# USB_UART.net
KiCad netlist of a schematic drawn in Altium Designer
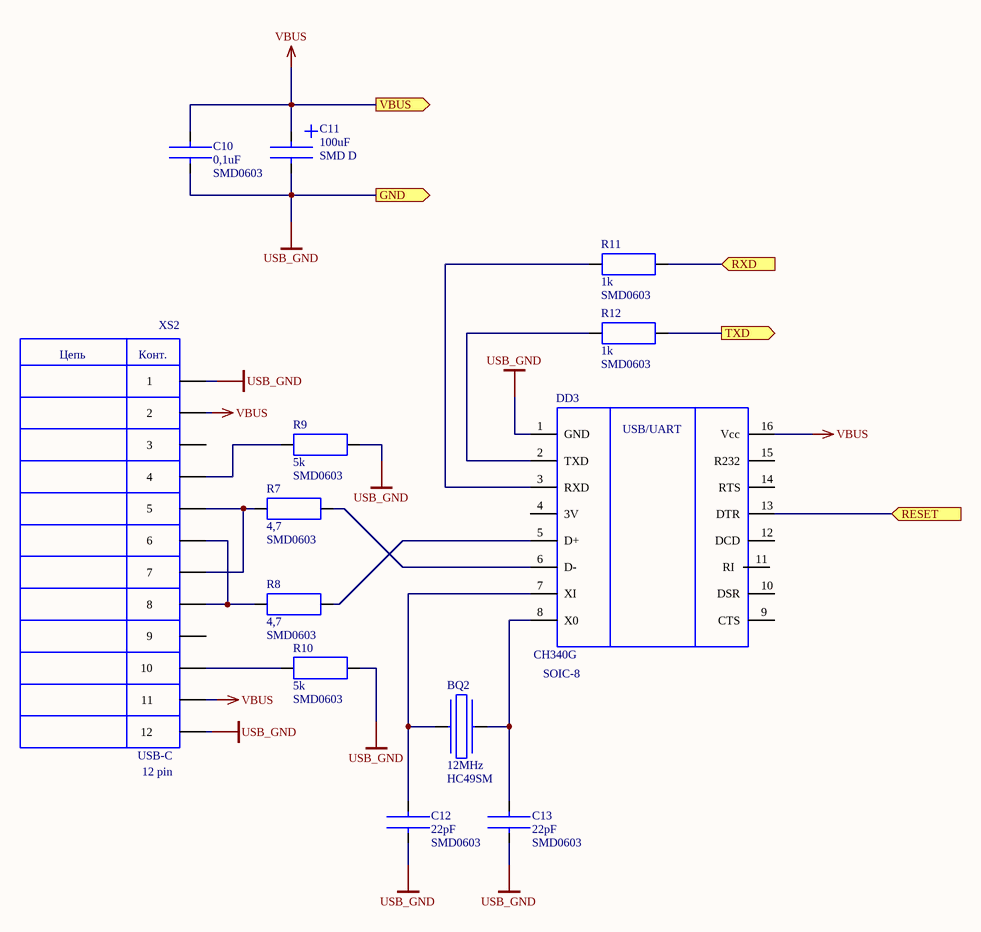
[diagram p0: USB_UART.SchDoc]

(export (version "E")
  (design (tool "Eeschema 10.0.6"))
  (components
    (comp (ref "BQ2")
      (value "12МHz")
      (footprint "BQ_HC49SM")
      (fields (field (name "PACKAGE") "HC49SM"))
      (libsource (lib "MechanikLibrary") (part "BQ_HC49SM"))
    )
    (comp (ref "C10")
      (value "0,1uF")
      (footprint "SMD0603(1005)")
      (fields (field (name "PACKAGE") "SMD0603"))
      (libsource (lib "MechanikLibrary") (part "CER_CUP_0603"))
    )
    (comp (ref "C11")
      (value "100uF")
      (footprint "TANT_CAP_D(7343)")
      (fields (field (name "PACKAGE") "SMD D"))
      (libsource (lib "MechanikLibrary") (part "C_TANT_D"))
    )
    (comp (ref "C12")
      (value "22pF")
      (footprint "SMD0603(1005)")
      (fields (field (name "PACKAGE") "SMD0603"))
      (libsource (lib "MechanikLibrary") (part "CER_CUP_0603"))
    )
    (comp (ref "C13")
      (value "22pF")
      (footprint "SMD0603(1005)")
      (fields (field (name "PACKAGE") "SMD0603"))
      (libsource (lib "MechanikLibrary") (part "CER_CUP_0603"))
    )
    (comp (ref "DD3")
      (value "CH340G")
      (footprint "SOIC16")
      (fields (field (name "PACKAGE") "SOIC-8"))
      (libsource (lib "MechanikLibrary") (part "Микросхема CH340G"))
    )
    (comp (ref "R7")
      (value "4,7")
      (footprint "SMD0603(1005)")
      (fields (field (name "PACKAGE") "SMD0603"))
      (libsource (lib "MechanikLibrary") (part "R_0603"))
    )
    (comp (ref "R8")
      (value "4,7")
      (footprint "SMD0603(1005)")
      (fields (field (name "PACKAGE") "SMD0603"))
      (libsource (lib "MechanikLibrary") (part "R_0603"))
    )
    (comp (ref "R9")
      (value "5k")
      (footprint "SMD0603(1005)")
      (fields (field (name "PACKAGE") "SMD0603"))
      (libsource (lib "MechanikLibrary") (part "R_0603"))
    )
    (comp (ref "R10")
      (value "5k")
      (footprint "SMD0603(1005)")
      (fields (field (name "PACKAGE") "SMD0603"))
      (libsource (lib "MechanikLibrary") (part "R_0603"))
    )
    (comp (ref "R11")
      (value "1k")
      (footprint "SMD0603(1005)")
      (fields (field (name "PACKAGE") "SMD0603"))
      (libsource (lib "MechanikLibrary") (part "R_0603"))
    )
    (comp (ref "R12")
      (value "1k")
      (footprint "SMD0603(1005)")
      (fields (field (name "PACKAGE") "SMD0603"))
      (libsource (lib "MechanikLibrary") (part "R_0603"))
    )
    (comp (ref "XS2")
      (value "USB-C")
      (footprint "USB_C")
      (fields (field (name "PACKAGE") "12 pin"))
      (libsource (lib "MechanikLibrary") (part "USB_C"))
    )
  )
  (nets
    (net (code "1") (name "/RESET") (class "Default")
      (node (ref "DD3") (pin "13") (pinfunction "DTR_13") (pintype "passive"))
    )
    (net (code "2") (name "/RXD") (class "Default") (node (ref "R11") (pin "1") (pintype "passive")))
    (net (code "3") (name "/TXD") (class "Default") (node (ref "R12") (pin "1") (pintype "passive")))
    (net (code "4") (name "Net-(DD3-D+)") (class "Default")
      (node (ref "DD3") (pin "5") (pinfunction "D+_5") (pintype "passive"))
      (node (ref "R8") (pin "2") (pintype "passive"))
    )
    (net (code "5") (name "Net-(DD3-D-)") (class "Default")
      (node (ref "DD3") (pin "6") (pinfunction "D-_6") (pintype "passive"))
      (node (ref "R7") (pin "2") (pintype "passive"))
    )
    (net (code "6") (name "Net-(DD3-RXD)") (class "Default")
      (node (ref "DD3") (pin "3") (pinfunction "RXD_3") (pintype "passive"))
      (node (ref "R11") (pin "2") (pintype "passive"))
    )
    (net (code "7") (name "Net-(DD3-TXD)") (class "Default")
      (node (ref "DD3") (pin "2") (pinfunction "TXD_2") (pintype "passive"))
      (node (ref "R12") (pin "2") (pintype "passive"))
    )
    (net (code "8") (name "Net-(DD3-X0)") (class "Default")
      (node (ref "BQ2") (pin "2") (pintype "passive"))
      (node (ref "C13") (pin "2") (pintype "passive"))
      (node (ref "DD3") (pin "8") (pinfunction "X0_8") (pintype "passive"))
    )
    (net (code "9") (name "Net-(DD3-XI)") (class "Default")
      (node (ref "BQ2") (pin "1") (pintype "passive"))
      (node (ref "C12") (pin "2") (pintype "passive"))
      (node (ref "DD3") (pin "7") (pinfunction "XI_7") (pintype "passive"))
    )
    (net (code "10") (name "Net-(R7-Pad1)") (class "Default")
      (node (ref "R7") (pin "1") (pintype "passive"))
      (node (ref "XS2") (pin "5") (pinfunction "5_5") (pintype "passive"))
      (node (ref "XS2") (pin "7") (pinfunction "7_7") (pintype "passive"))
    )
    (net (code "11") (name "Net-(R8-Pad1)") (class "Default")
      (node (ref "R8") (pin "1") (pintype "passive"))
      (node (ref "XS2") (pin "6") (pinfunction "6_6") (pintype "passive"))
      (node (ref "XS2") (pin "8") (pinfunction "8_8") (pintype "passive"))
    )
    (net (code "12") (name "Net-(R9-Pad2)") (class "Default")
      (node (ref "R9") (pin "2") (pintype "passive"))
      (node (ref "XS2") (pin "4") (pinfunction "4_4") (pintype "passive"))
    )
    (net (code "13") (name "Net-(R10-Pad2)") (class "Default")
      (node (ref "R10") (pin "2") (pintype "passive"))
      (node (ref "XS2") (pin "10") (pinfunction "10_10") (pintype "passive"))
    )
    (net (code "14") (name "USB_GND") (class "Default")
      (node (ref "C10") (pin "1") (pintype "passive"))
      (node (ref "C11") (pin "2") (pintype "passive"))
      (node (ref "C12") (pin "1") (pintype "passive"))
      (node (ref "C13") (pin "1") (pintype "passive"))
      (node (ref "DD3") (pin "1") (pinfunction "GND_1") (pintype "passive"))
      (node (ref "R10") (pin "1") (pintype "passive"))
      (node (ref "R9") (pin "1") (pintype "passive"))
      (node (ref "XS2") (pin "1") (pinfunction "1_1") (pintype "passive"))
      (node (ref "XS2") (pin "12") (pinfunction "12_12") (pintype "passive"))
    )
    (net (code "15") (name "VBUS") (class "Default")
      (node (ref "C10") (pin "2") (pintype "passive"))
      (node (ref "C11") (pin "1") (pintype "passive"))
      (node (ref "DD3") (pin "16") (pinfunction "Vcc_16") (pintype "passive"))
      (node (ref "XS2") (pin "11") (pinfunction "11_11") (pintype "passive"))
      (node (ref "XS2") (pin "2") (pinfunction "2_2") (pintype "passive"))
    )
    (net (code "16") (name "unconnected-(DD3-3V-Pad4)") (class "Default")
      (node (ref "DD3") (pin "4") (pinfunction "3V_4") (pintype "passive"))
    )
    (net (code "17") (name "unconnected-(DD3-CTS-Pad9)") (class "Default")
      (node (ref "DD3") (pin "9") (pinfunction "CTS_9") (pintype "passive"))
    )
    (net (code "18") (name "unconnected-(DD3-DCD-Pad12)") (class "Default")
      (node (ref "DD3") (pin "12") (pinfunction "DCD_12") (pintype "passive"))
    )
    (net (code "19") (name "unconnected-(DD3-DSR-Pad10)") (class "Default")
      (node (ref "DD3") (pin "10") (pinfunction "DSR_10") (pintype "passive"))
    )
    (net (code "20") (name "unconnected-(DD3-R232-Pad15)") (class "Default")
      (node (ref "DD3") (pin "15") (pinfunction "R232_15") (pintype "passive"))
    )
    (net (code "21") (name "unconnected-(DD3-RI-Pad11)") (class "Default")
      (node (ref "DD3") (pin "11") (pinfunction "RI_11") (pintype "passive"))
    )
    (net (code "22") (name "unconnected-(DD3-RTS-Pad14)") (class "Default")
      (node (ref "DD3") (pin "14") (pinfunction "RTS_14") (pintype "passive"))
    )
    (net (code "23") (name "unconnected-(XS2-Pad3)") (class "Default")
      (node (ref "XS2") (pin "3") (pinfunction "3_3") (pintype "passive"))
    )
    (net (code "24") (name "unconnected-(XS2-Pad9)") (class "Default")
      (node (ref "XS2") (pin "9") (pinfunction "9_9") (pintype "passive"))
    )
  )
)
